# P05_SDRAM.net
KiCad netlist of a schematic drawn in Altium Designer
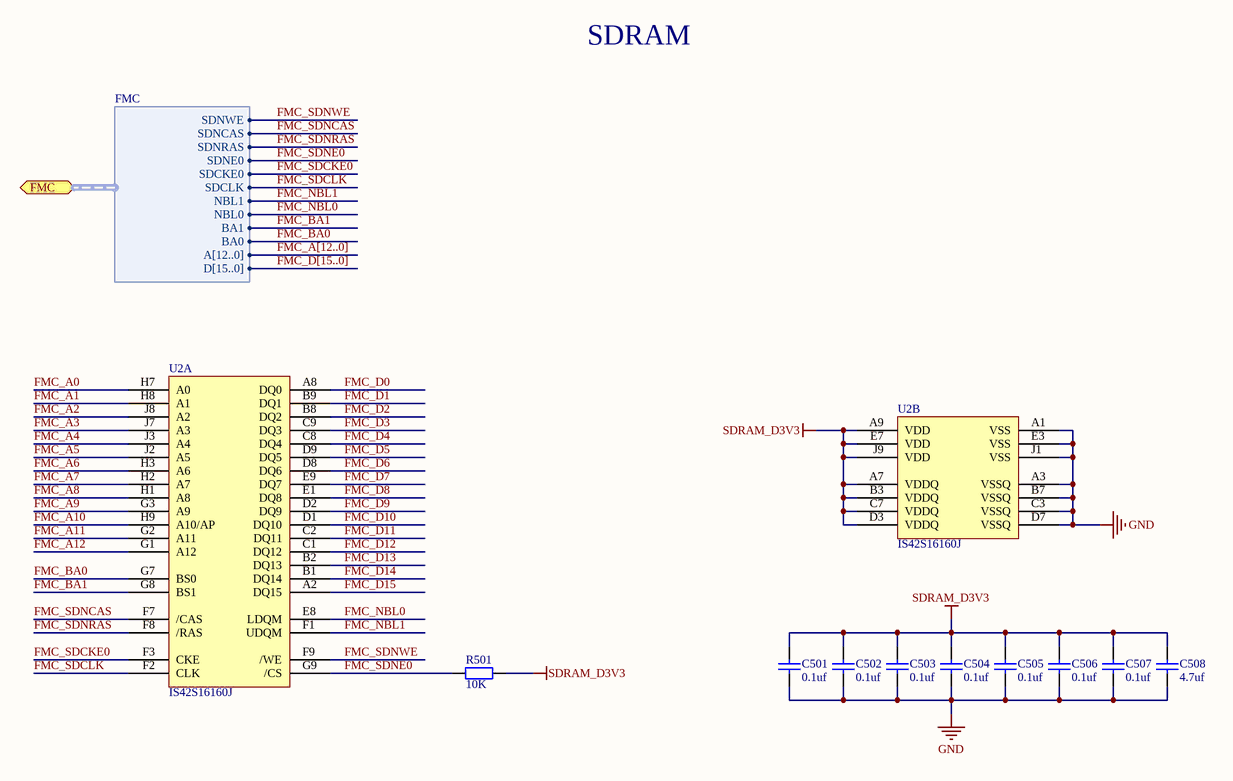
[diagram p0: P05.SDRAM.SchDoc]

(export (version "E")
  (design (tool "Eeschema 10.0.6"))
  (components
    (comp (ref "C501")
      (value "0.1uf")
      (footprint "C0402")
      (fields (field (name "Comment") "Cap"))
      (libsource (lib "carrot_lib") (part "Cap"))
    )
    (comp (ref "C502")
      (value "0.1uf")
      (footprint "C0402")
      (fields (field (name "Comment") "Cap"))
      (libsource (lib "carrot_lib") (part "Cap"))
    )
    (comp (ref "C503")
      (value "0.1uf")
      (footprint "C0402")
      (fields (field (name "Comment") "Cap"))
      (libsource (lib "carrot_lib") (part "Cap"))
    )
    (comp (ref "C504")
      (value "0.1uf")
      (footprint "C0402")
      (fields (field (name "Comment") "Cap"))
      (libsource (lib "carrot_lib") (part "Cap"))
    )
    (comp (ref "C505")
      (value "0.1uf")
      (footprint "C0402")
      (fields (field (name "Comment") "Cap"))
      (libsource (lib "carrot_lib") (part "Cap"))
    )
    (comp (ref "C506")
      (value "0.1uf")
      (footprint "C0402")
      (fields (field (name "Comment") "Cap"))
      (libsource (lib "carrot_lib") (part "Cap"))
    )
    (comp (ref "C507")
      (value "0.1uf")
      (footprint "C0402")
      (fields (field (name "Comment") "Cap"))
      (libsource (lib "carrot_lib") (part "Cap"))
    )
    (comp (ref "C508")
      (value "4.7uf")
      (footprint "C0603")
      (fields (field (name "Comment") "Cap"))
      (libsource (lib "carrot_lib") (part "Cap"))
    )
    (comp (ref "R501")
      (value "10K")
      (footprint "R0603")
      (description "电阻")
      (fields (field (name "Comment") "Res"))
      (libsource (lib "carrot_lib") (part "Res"))
    )
    (comp (ref "U2")
      (value "IS42S16160J")
      (footprint "IS42S16160J-TFBGA54")
      (description "32Meg x 8, 16Meg x16, 256Mb SYNCHRONOUS DRAM")
      (libsource (lib "carrot_lib") (part "IS42S16160J"))
    )
  )
  (nets
    (net (code "2") (name "/FMC_A0") (class "Default")
      (node (ref "U2") (pin "H7") (pinfunction "A0_H7") (pintype "passive"))
    )
    (net (code "3") (name "/FMC_A1") (class "Default")
      (node (ref "U2") (pin "H8") (pinfunction "A1_H8") (pintype "passive"))
    )
    (net (code "4") (name "/FMC_A2") (class "Default")
      (node (ref "U2") (pin "J8") (pinfunction "A2_J8") (pintype "passive"))
    )
    (net (code "5") (name "/FMC_A3") (class "Default")
      (node (ref "U2") (pin "J7") (pinfunction "A3_J7") (pintype "passive"))
    )
    (net (code "6") (name "/FMC_A4") (class "Default")
      (node (ref "U2") (pin "J3") (pinfunction "A4_J3") (pintype "passive"))
    )
    (net (code "7") (name "/FMC_A5") (class "Default")
      (node (ref "U2") (pin "J2") (pinfunction "A5_J2") (pintype "passive"))
    )
    (net (code "8") (name "/FMC_A6") (class "Default")
      (node (ref "U2") (pin "H3") (pinfunction "A6_H3") (pintype "passive"))
    )
    (net (code "9") (name "/FMC_A7") (class "Default")
      (node (ref "U2") (pin "H2") (pinfunction "A7_H2") (pintype "passive"))
    )
    (net (code "10") (name "/FMC_A8") (class "Default")
      (node (ref "U2") (pin "H1") (pinfunction "A8_H1") (pintype "passive"))
    )
    (net (code "11") (name "/FMC_A9") (class "Default")
      (node (ref "U2") (pin "G3") (pinfunction "A9_G3") (pintype "passive"))
    )
    (net (code "12") (name "/FMC_A10") (class "Default")
      (node (ref "U2") (pin "H9") (pinfunction "A10/AP_H9") (pintype "passive"))
    )
    (net (code "13") (name "/FMC_A11") (class "Default")
      (node (ref "U2") (pin "G2") (pinfunction "A11_G2") (pintype "passive"))
    )
    (net (code "14") (name "/FMC_A12") (class "Default")
      (node (ref "U2") (pin "G1") (pinfunction "A12_G1") (pintype "passive"))
    )
    (net (code "15") (name "/FMC_BA0") (class "Default")
      (node (ref "U2") (pin "G7") (pinfunction "BS0_G7") (pintype "passive"))
    )
    (net (code "16") (name "/FMC_BA1") (class "Default")
      (node (ref "U2") (pin "G8") (pinfunction "BS1_G8") (pintype "passive"))
    )
    (net (code "17") (name "/FMC_D0") (class "Default")
      (node (ref "U2") (pin "A8") (pinfunction "DQ0_A8") (pintype "passive"))
    )
    (net (code "18") (name "/FMC_D1") (class "Default")
      (node (ref "U2") (pin "B9") (pinfunction "DQ1_B9") (pintype "passive"))
    )
    (net (code "19") (name "/FMC_D2") (class "Default")
      (node (ref "U2") (pin "B8") (pinfunction "DQ2_B8") (pintype "passive"))
    )
    (net (code "20") (name "/FMC_D3") (class "Default")
      (node (ref "U2") (pin "C9") (pinfunction "DQ3_C9") (pintype "passive"))
    )
    (net (code "21") (name "/FMC_D4") (class "Default")
      (node (ref "U2") (pin "C8") (pinfunction "DQ4_C8") (pintype "passive"))
    )
    (net (code "22") (name "/FMC_D5") (class "Default")
      (node (ref "U2") (pin "D9") (pinfunction "DQ5_D9") (pintype "passive"))
    )
    (net (code "23") (name "/FMC_D6") (class "Default")
      (node (ref "U2") (pin "D8") (pinfunction "DQ6_D8") (pintype "passive"))
    )
    (net (code "24") (name "/FMC_D7") (class "Default")
      (node (ref "U2") (pin "E9") (pinfunction "DQ7_E9") (pintype "passive"))
    )
    (net (code "25") (name "/FMC_D8") (class "Default")
      (node (ref "U2") (pin "E1") (pinfunction "DQ8_E1") (pintype "passive"))
    )
    (net (code "26") (name "/FMC_D9") (class "Default")
      (node (ref "U2") (pin "D2") (pinfunction "DQ9_D2") (pintype "passive"))
    )
    (net (code "27") (name "/FMC_D10") (class "Default")
      (node (ref "U2") (pin "D1") (pinfunction "DQ10_D1") (pintype "passive"))
    )
    (net (code "28") (name "/FMC_D11") (class "Default")
      (node (ref "U2") (pin "C2") (pinfunction "DQ11_C2") (pintype "passive"))
    )
    (net (code "29") (name "/FMC_D12") (class "Default")
      (node (ref "U2") (pin "C1") (pinfunction "DQ12_C1") (pintype "passive"))
    )
    (net (code "30") (name "/FMC_D13") (class "Default")
      (node (ref "U2") (pin "B2") (pinfunction "DQ13_B2") (pintype "passive"))
    )
    (net (code "31") (name "/FMC_D14") (class "Default")
      (node (ref "U2") (pin "B1") (pinfunction "DQ14_B1") (pintype "passive"))
    )
    (net (code "32") (name "/FMC_D15") (class "Default")
      (node (ref "U2") (pin "A2") (pinfunction "DQ15_A2") (pintype "passive"))
    )
    (net (code "34") (name "/FMC_NBL0") (class "Default")
      (node (ref "U2") (pin "E8") (pinfunction "LDQM_E8") (pintype "passive"))
    )
    (net (code "35") (name "/FMC_NBL1") (class "Default")
      (node (ref "U2") (pin "F1") (pinfunction "UDQM_F1") (pintype "passive"))
    )
    (net (code "36") (name "/FMC_SDCKE0") (class "Default")
      (node (ref "U2") (pin "F3") (pinfunction "CKE_F3") (pintype "passive"))
    )
    (net (code "37") (name "/FMC_SDCLK") (class "Default")
      (node (ref "U2") (pin "F2") (pinfunction "CLK_F2") (pintype "passive"))
    )
    (net (code "38") (name "/FMC_SDNCAS") (class "Default")
      (node (ref "U2") (pin "F7") (pinfunction "/CAS_F7") (pintype "passive"))
    )
    (net (code "39") (name "/FMC_SDNE0") (class "Default")
      (node (ref "R501") (pin "1") (pinfunction "1_1") (pintype "passive"))
      (node (ref "U2") (pin "G9") (pinfunction "/CS_G9") (pintype "passive"))
    )
    (net (code "40") (name "/FMC_SDNRAS") (class "Default")
      (node (ref "U2") (pin "F8") (pinfunction "/RAS_F8") (pintype "passive"))
    )
    (net (code "41") (name "/FMC_SDNWE") (class "Default")
      (node (ref "U2") (pin "F9") (pinfunction "/WE_F9") (pintype "passive"))
    )
    (net (code "44") (name "GND") (class "Default")
      (node (ref "C501") (pin "1") (pinfunction "1_1") (pintype "passive"))
      (node (ref "C502") (pin "1") (pinfunction "1_1") (pintype "passive"))
      (node (ref "C503") (pin "1") (pinfunction "1_1") (pintype "passive"))
      (node (ref "C504") (pin "1") (pinfunction "1_1") (pintype "passive"))
      (node (ref "C505") (pin "1") (pinfunction "1_1") (pintype "passive"))
      (node (ref "C506") (pin "1") (pinfunction "1_1") (pintype "passive"))
      (node (ref "C507") (pin "1") (pinfunction "1_1") (pintype "passive"))
      (node (ref "C508") (pin "1") (pinfunction "1_1") (pintype "passive"))
      (node (ref "U2") (pin "A1") (pinfunction "VSS_A1") (pintype "passive"))
      (node (ref "U2") (pin "A3") (pinfunction "VSSQ_A3") (pintype "passive"))
      (node (ref "U2") (pin "B7") (pinfunction "VSSQ_B7") (pintype "passive"))
      (node (ref "U2") (pin "C3") (pinfunction "VSSQ_C3") (pintype "passive"))
      (node (ref "U2") (pin "D7") (pinfunction "VSSQ_D7") (pintype "passive"))
      (node (ref "U2") (pin "E3") (pinfunction "VSS_E3") (pintype "passive"))
      (node (ref "U2") (pin "J1") (pinfunction "VSS_J1") (pintype "passive"))
    )
    (net (code "45") (name "SDRAM_D3V3") (class "Default")
      (node (ref "C501") (pin "2") (pinfunction "2_2") (pintype "passive"))
      (node (ref "C502") (pin "2") (pinfunction "2_2") (pintype "passive"))
      (node (ref "C503") (pin "2") (pinfunction "2_2") (pintype "passive"))
      (node (ref "C504") (pin "2") (pinfunction "2_2") (pintype "passive"))
      (node (ref "C505") (pin "2") (pinfunction "2_2") (pintype "passive"))
      (node (ref "C506") (pin "2") (pinfunction "2_2") (pintype "passive"))
      (node (ref "C507") (pin "2") (pinfunction "2_2") (pintype "passive"))
      (node (ref "C508") (pin "2") (pinfunction "2_2") (pintype "passive"))
      (node (ref "R501") (pin "2") (pinfunction "2_2") (pintype "passive"))
      (node (ref "U2") (pin "A7") (pinfunction "VDDQ_A7") (pintype "passive"))
      (node (ref "U2") (pin "A9") (pinfunction "VDD_A9") (pintype "passive"))
      (node (ref "U2") (pin "B3") (pinfunction "VDDQ_B3") (pintype "passive"))
      (node (ref "U2") (pin "C7") (pinfunction "VDDQ_C7") (pintype "passive"))
      (node (ref "U2") (pin "D3") (pinfunction "VDDQ_D3") (pintype "passive"))
      (node (ref "U2") (pin "E7") (pinfunction "VDD_E7") (pintype "passive"))
      (node (ref "U2") (pin "J9") (pinfunction "VDD_J9") (pintype "passive"))
    )
  )
)
